# PDInjector.net
KiCad netlist of a schematic drawn in Altium Designer
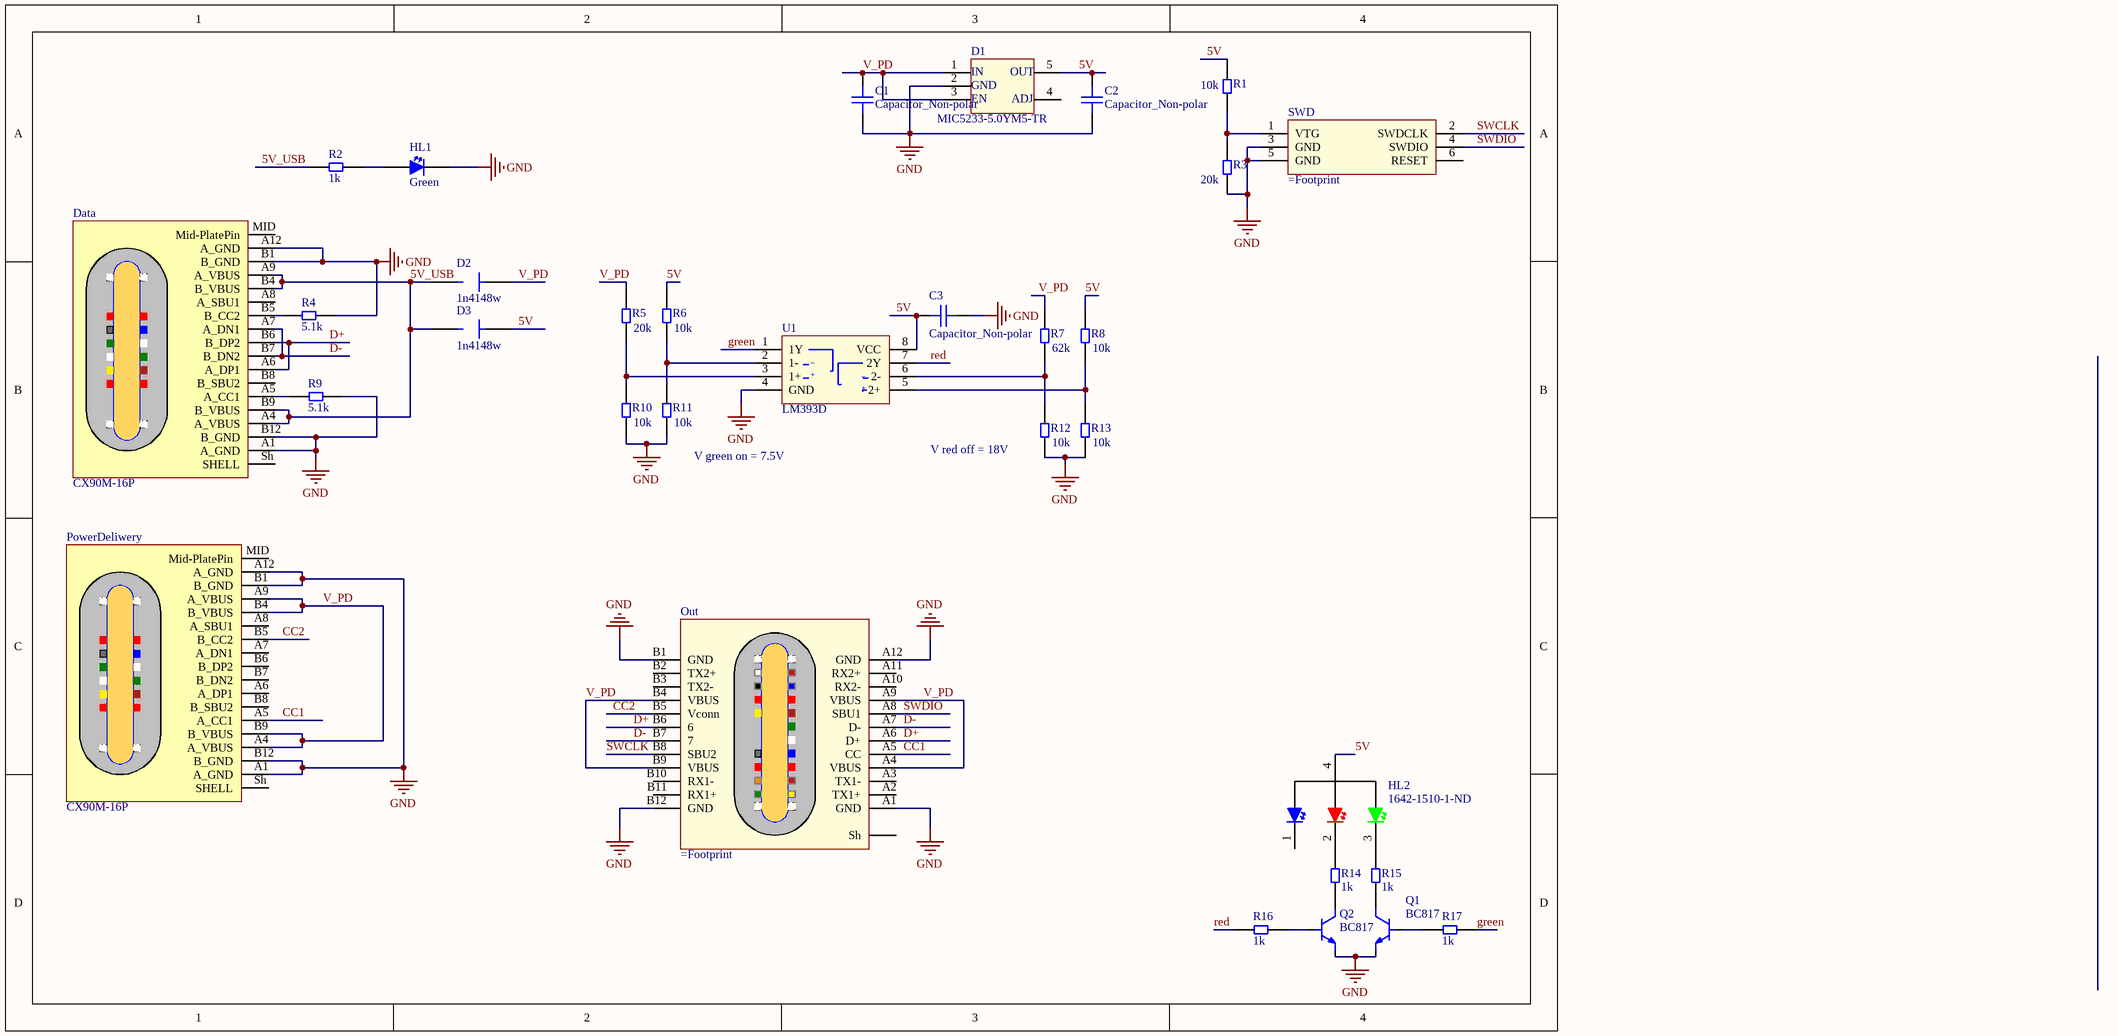
[diagram p0: PDInjector.SchDoc]

(export (version "E")
  (design (tool "Eeschema 10.0.6"))
  (components
    (comp (ref "C1")
      (value "Capacitor_Non-polar")
      (footprint "CAP_0402")
      (libsource (lib "PassiveComponents") (part "Capacitor_Non-polar"))
    )
    (comp (ref "C2")
      (value "Capacitor_Non-polar")
      (footprint "CAP_0402")
      (libsource (lib "PassiveComponents") (part "Capacitor_Non-polar"))
    )
    (comp (ref "C3")
      (value "Capacitor_Non-polar")
      (footprint "CAP_0402")
      (libsource (lib "PassiveComponents") (part "Capacitor_Non-polar"))
    )
    (comp (ref "D1")
      (value "MIC5233-5.0YM5-TR")
      (footprint "SOT23-5")
      (libsource (lib "PowerSupply lib ") (part "MIC5233-3.3YM5-TR LDO"))
    )
    (comp (ref "D2")
      (value "1n4148w")
      (footprint "SOD-123FL")
      (description "Different types of diodes")
      (libsource (lib "Semiconductors-Discretes") (part "DIOD"))
    )
    (comp (ref "D3")
      (value "1n4148w")
      (footprint "SOD-123FL")
      (description "Different types of diodes")
      (libsource (lib "Semiconductors-Discretes") (part "DIOD"))
    )
    (comp (ref "Data")
      (value "CX90M-16P")
      (footprint "USB_C_Hirose_CX90M-16P")
      (libsource (lib "Connectors") (part "USB_C_Hirose_CX90M-16P"))
    )
    (comp (ref "HL1")
      (value "Green")
      (footprint "LED_0603")
      (libsource (lib "OptoelectronicsDisplays") (part "SMD_LED"))
    )
    (comp (ref "HL2")
      (value "1642-1510-1-ND")
      (footprint "CL-505S-X-SD-T")
      (libsource (lib "OptoelectronicsDisplays") (part "1642-1510-1-ND"))
    )
    (comp (ref "Out")
      (value "~")
      (footprint "USB_TYPE-C_PLUG")
      (libsource (lib "Connectors") (part "USB Type-C Plug"))
    )
    (comp (ref "PowerDeliwery")
      (value "CX90M-16P")
      (footprint "USB_C_Hirose_CX90M-16P")
      (libsource (lib "Connectors") (part "USB_C_Hirose_CX90M-16P"))
    )
    (comp (ref "Q1")
      (value "BC817")
      (footprint "SOT23")
      (description "Transistor_NPN_SOT-23")
      (libsource (lib "Semiconductors-Discretes") (part "Transistor_NPN_SOT-23"))
    )
    (comp (ref "Q2")
      (value "BC817")
      (footprint "SOT23")
      (description "Transistor_NPN_SOT-23")
      (libsource (lib "Semiconductors-Discretes") (part "Transistor_NPN_SOT-23"))
    )
    (comp (ref "R1")
      (value "10k")
      (footprint "RES_0402")
      (libsource (lib "PassiveComponents") (part "Resistor"))
    )
    (comp (ref "R2")
      (value "1k")
      (footprint "RES_0402")
      (libsource (lib "PassiveComponents") (part "Resistor"))
    )
    (comp (ref "R3")
      (value "20k")
      (footprint "RES_0402")
      (libsource (lib "PassiveComponents") (part "Resistor"))
    )
    (comp (ref "R4")
      (value "5.1k")
      (footprint "RES_0402")
      (libsource (lib "PassiveComponents") (part "Resistor"))
    )
    (comp (ref "R5")
      (value "20k")
      (footprint "RES_0402")
      (libsource (lib "PassiveComponents") (part "Resistor"))
    )
    (comp (ref "R6")
      (value "10k")
      (footprint "RES_0402")
      (libsource (lib "PassiveComponents") (part "Resistor"))
    )
    (comp (ref "R7")
      (value "62k")
      (footprint "RES_0402")
      (libsource (lib "PassiveComponents") (part "Resistor"))
    )
    (comp (ref "R8")
      (value "10k")
      (footprint "RES_0402")
      (libsource (lib "PassiveComponents") (part "Resistor"))
    )
    (comp (ref "R9")
      (value "5.1k")
      (footprint "RES_0402")
      (libsource (lib "PassiveComponents") (part "Resistor"))
    )
    (comp (ref "R10")
      (value "10k")
      (footprint "RES_0402")
      (libsource (lib "PassiveComponents") (part "Resistor"))
    )
    (comp (ref "R11")
      (value "10k")
      (footprint "RES_0402")
      (libsource (lib "PassiveComponents") (part "Resistor"))
    )
    (comp (ref "R12")
      (value "10k")
      (footprint "RES_0402")
      (libsource (lib "PassiveComponents") (part "Resistor"))
    )
    (comp (ref "R13")
      (value "10k")
      (footprint "RES_0402")
      (libsource (lib "PassiveComponents") (part "Resistor"))
    )
    (comp (ref "R14")
      (value "1k")
      (footprint "RES_0402")
      (libsource (lib "PassiveComponents") (part "Resistor"))
    )
    (comp (ref "R15")
      (value "1k")
      (footprint "RES_0402")
      (libsource (lib "PassiveComponents") (part "Resistor"))
    )
    (comp (ref "R16")
      (value "1k")
      (footprint "RES_0402")
      (libsource (lib "PassiveComponents") (part "Resistor"))
    )
    (comp (ref "R17")
      (value "1k")
      (footprint "RES_0402")
      (libsource (lib "PassiveComponents") (part "Resistor"))
    )
    (comp (ref "SWD")
      (value "~")
      (footprint "MICRO-MATCH FOB.06P")
      (libsource (lib "Connectors") (part "MICRO-MATCH FOB.06P_nRF/STM32_SWD"))
    )
    (comp (ref "U1")
      (value "LM393D")
      (footprint "SOIC8(3.9)")
      (description "Dual OpAmp")
      (libsource (lib "AmplifiersAndComparators") (part "LM358"))
    )
  )
  (nets
    (net (code "1") (name "/5V") (class "Default")
      (node (ref "C2") (pin "2") (pinfunction "2_2") (pintype "passive"))
      (node (ref "C3") (pin "1") (pinfunction "1_1") (pintype "passive"))
      (node (ref "D1") (pin "5") (pintype "power_in"))
      (node (ref "D3") (pin "2") (pinfunction "Cathode_2") (pintype "passive"))
      (node (ref "HL2") (pin "4") (pinfunction "4_4") (pintype "passive"))
      (node (ref "R1") (pin "2") (pinfunction "2_2") (pintype "passive"))
      (node (ref "R6") (pin "2") (pinfunction "2_2") (pintype "passive"))
      (node (ref "R8") (pin "2") (pinfunction "2_2") (pintype "passive"))
      (node (ref "U1") (pin "8") (pinfunction "VCC_8") (pintype "passive"))
    )
    (net (code "2") (name "/5V_USB") (class "Default")
      (node (ref "D2") (pin "1") (pinfunction "Anode_1") (pintype "passive"))
      (node (ref "D3") (pin "1") (pinfunction "Anode_1") (pintype "passive"))
      (node (ref "Data") (pin "A4") (pinfunction "A_VBUS_A4") (pintype "passive"))
      (node (ref "Data") (pin "A9") (pinfunction "A_VBUS_A9") (pintype "passive"))
      (node (ref "Data") (pin "B4") (pinfunction "B_VBUS_B4") (pintype "passive"))
      (node (ref "Data") (pin "B9") (pinfunction "B_VBUS_B9") (pintype "passive"))
      (node (ref "R2") (pin "2") (pinfunction "2_2") (pintype "passive"))
    )
    (net (code "3") (name "/CC1") (class "Default")
      (node (ref "Out") (pin "A5") (pinfunction "CC_A5") (pintype "passive"))
      (node (ref "PowerDeliwery") (pin "A5") (pinfunction "A_CC1_A5") (pintype "passive"))
    )
    (net (code "4") (name "/CC2") (class "Default")
      (node (ref "Out") (pin "B5") (pinfunction "Vconn_B5") (pintype "passive"))
      (node (ref "PowerDeliwery") (pin "B5") (pinfunction "B_CC2_B5") (pintype "passive"))
    )
    (net (code "5") (name "/D+") (class "Default")
      (node (ref "Data") (pin "A6") (pinfunction "A_DP1_A6") (pintype "passive"))
      (node (ref "Data") (pin "B6") (pinfunction "B_DP2_B6") (pintype "passive"))
      (node (ref "Out") (pin "A6") (pinfunction "D+_A6") (pintype "passive"))
      (node (ref "Out") (pin "B6") (pinfunction "6_B6") (pintype "passive"))
    )
    (net (code "6") (name "/D-") (class "Default")
      (node (ref "Data") (pin "A7") (pinfunction "A_DN1_A7") (pintype "passive"))
      (node (ref "Data") (pin "B7") (pinfunction "B_DN2_B7") (pintype "passive"))
      (node (ref "Out") (pin "A7") (pinfunction "D-_A7") (pintype "passive"))
      (node (ref "Out") (pin "B7") (pinfunction "7_B7") (pintype "passive"))
    )
    (net (code "7") (name "/SWCLK") (class "Default")
      (node (ref "Out") (pin "B8") (pinfunction "SBU2_B8") (pintype "passive"))
      (node (ref "SWD") (pin "2") (pinfunction "SWDCLK_2") (pintype "passive"))
    )
    (net (code "8") (name "/SWDIO") (class "Default")
      (node (ref "Out") (pin "A8") (pinfunction "SBU1_A8") (pintype "passive"))
      (node (ref "SWD") (pin "4") (pinfunction "SWDIO_4") (pintype "passive"))
    )
    (net (code "9") (name "/V_PD") (class "Default")
      (node (ref "C1") (pin "2") (pinfunction "2_2") (pintype "passive"))
      (node (ref "D1") (pin "1") (pintype "power_in"))
      (node (ref "D1") (pin "3") (pintype "power_in"))
      (node (ref "D2") (pin "2") (pinfunction "Cathode_2") (pintype "passive"))
      (node (ref "Out") (pin "A4") (pinfunction "VBUS_A4") (pintype "passive"))
      (node (ref "Out") (pin "A9") (pinfunction "VBUS_A9") (pintype "passive"))
      (node (ref "Out") (pin "B4") (pinfunction "VBUS_B4") (pintype "passive"))
      (node (ref "Out") (pin "B9") (pinfunction "VBUS_B9") (pintype "passive"))
      (node (ref "PowerDeliwery") (pin "A4") (pinfunction "A_VBUS_A4") (pintype "passive"))
      (node (ref "PowerDeliwery") (pin "A9") (pinfunction "A_VBUS_A9") (pintype "passive"))
      (node (ref "PowerDeliwery") (pin "B4") (pinfunction "B_VBUS_B4") (pintype "passive"))
      (node (ref "PowerDeliwery") (pin "B9") (pinfunction "B_VBUS_B9") (pintype "passive"))
      (node (ref "R5") (pin "2") (pinfunction "2_2") (pintype "passive"))
      (node (ref "R7") (pin "2") (pinfunction "2_2") (pintype "passive"))
    )
    (net (code "10") (name "/green") (class "Default")
      (node (ref "R17") (pin "2") (pinfunction "2_2") (pintype "passive"))
      (node (ref "U1") (pin "1") (pinfunction "1Y_1") (pintype "passive"))
    )
    (net (code "11") (name "/red") (class "Default")
      (node (ref "R16") (pin "1") (pinfunction "1_1") (pintype "passive"))
      (node (ref "U1") (pin "7") (pinfunction "2Y_7") (pintype "passive"))
    )
    (net (code "12") (name "GND") (class "Default")
      (node (ref "C1") (pin "1") (pinfunction "1_1") (pintype "passive"))
      (node (ref "C2") (pin "1") (pinfunction "1_1") (pintype "passive"))
      (node (ref "C3") (pin "2") (pinfunction "2_2") (pintype "passive"))
      (node (ref "D1") (pin "2") (pintype "power_in"))
      (node (ref "Data") (pin "A1") (pinfunction "A_GND_A1") (pintype "passive"))
      (node (ref "Data") (pin "A12") (pinfunction "A_GND_A12") (pintype "passive"))
      (node (ref "Data") (pin "B1") (pinfunction "B_GND_B1") (pintype "passive"))
      (node (ref "Data") (pin "B12") (pinfunction "B_GND_B12") (pintype "passive"))
      (node (ref "HL1") (pin "2") (pinfunction "2_2") (pintype "passive"))
      (node (ref "Out") (pin "A1") (pinfunction "GND_A1") (pintype "passive"))
      (node (ref "Out") (pin "A12") (pinfunction "GND_A12") (pintype "passive"))
      (node (ref "Out") (pin "B1") (pinfunction "GND_B1") (pintype "passive"))
      (node (ref "Out") (pin "B12") (pinfunction "GND_B12") (pintype "passive"))
      (node (ref "PowerDeliwery") (pin "A1") (pinfunction "A_GND_A1") (pintype "passive"))
      (node (ref "PowerDeliwery") (pin "A12") (pinfunction "A_GND_A12") (pintype "passive"))
      (node (ref "PowerDeliwery") (pin "B1") (pinfunction "B_GND_B1") (pintype "passive"))
      (node (ref "PowerDeliwery") (pin "B12") (pinfunction "B_GND_B12") (pintype "passive"))
      (node (ref "Q1") (pin "2") (pinfunction "E_2") (pintype "passive"))
      (node (ref "Q2") (pin "2") (pinfunction "E_2") (pintype "passive"))
      (node (ref "R10") (pin "1") (pinfunction "1_1") (pintype "passive"))
      (node (ref "R11") (pin "1") (pinfunction "1_1") (pintype "passive"))
      (node (ref "R12") (pin "1") (pinfunction "1_1") (pintype "passive"))
      (node (ref "R13") (pin "1") (pinfunction "1_1") (pintype "passive"))
      (node (ref "R3") (pin "1") (pinfunction "1_1") (pintype "passive"))
      (node (ref "R4") (pin "1") (pinfunction "1_1") (pintype "passive"))
      (node (ref "R9") (pin "1") (pinfunction "1_1") (pintype "passive"))
      (node (ref "SWD") (pin "3") (pinfunction "GND_3") (pintype "passive"))
      (node (ref "SWD") (pin "5") (pinfunction "GND_5") (pintype "passive"))
      (node (ref "U1") (pin "4") (pinfunction "GND_4") (pintype "passive"))
    )
    (net (code "13") (name "Net-(Data-A_CC1)") (class "Default")
      (node (ref "Data") (pin "A5") (pinfunction "A_CC1_A5") (pintype "passive"))
      (node (ref "R9") (pin "2") (pinfunction "2_2") (pintype "passive"))
    )
    (net (code "14") (name "Net-(Data-B_CC2)") (class "Default")
      (node (ref "Data") (pin "B5") (pinfunction "B_CC2_B5") (pintype "passive"))
      (node (ref "R4") (pin "2") (pinfunction "2_2") (pintype "passive"))
    )
    (net (code "15") (name "Net-(HL1-Pad1)") (class "Default")
      (node (ref "HL1") (pin "1") (pinfunction "1_1") (pintype "passive"))
      (node (ref "R2") (pin "1") (pinfunction "1_1") (pintype "passive"))
    )
    (net (code "16") (name "Net-(HL2-Pad2)") (class "Default")
      (node (ref "HL2") (pin "2") (pinfunction "2_2") (pintype "passive"))
      (node (ref "R14") (pin "1") (pinfunction "1_1") (pintype "passive"))
    )
    (net (code "17") (name "Net-(HL2-Pad3)") (class "Default")
      (node (ref "HL2") (pin "3") (pinfunction "3_3") (pintype "passive"))
      (node (ref "R15") (pin "1") (pinfunction "1_1") (pintype "passive"))
    )
    (net (code "18") (name "Net-(Q1-B)") (class "Default")
      (node (ref "Q1") (pin "1") (pinfunction "B_1") (pintype "passive"))
      (node (ref "R17") (pin "1") (pinfunction "1_1") (pintype "passive"))
    )
    (net (code "19") (name "Net-(Q1-C)") (class "Default")
      (node (ref "Q1") (pin "3") (pinfunction "C_3") (pintype "passive"))
      (node (ref "R15") (pin "2") (pinfunction "2_2") (pintype "passive"))
    )
    (net (code "20") (name "Net-(Q2-B)") (class "Default")
      (node (ref "Q2") (pin "1") (pinfunction "B_1") (pintype "passive"))
      (node (ref "R16") (pin "2") (pinfunction "2_2") (pintype "passive"))
    )
    (net (code "21") (name "Net-(Q2-C)") (class "Default")
      (node (ref "Q2") (pin "3") (pinfunction "C_3") (pintype "passive"))
      (node (ref "R14") (pin "2") (pinfunction "2_2") (pintype "passive"))
    )
    (net (code "22") (name "Net-(SWD-VTG)") (class "Default")
      (node (ref "R1") (pin "1") (pinfunction "1_1") (pintype "passive"))
      (node (ref "R3") (pin "2") (pinfunction "2_2") (pintype "passive"))
      (node (ref "SWD") (pin "1") (pinfunction "VTG_1") (pintype "passive"))
    )
    (net (code "23") (name "Net-(U1-1+)") (class "Default")
      (node (ref "R10") (pin "2") (pinfunction "2_2") (pintype "passive"))
      (node (ref "R5") (pin "1") (pinfunction "1_1") (pintype "passive"))
      (node (ref "U1") (pin "3") (pinfunction "1+_3") (pintype "passive"))
    )
    (net (code "24") (name "Net-(U1-1-)") (class "Default")
      (node (ref "R11") (pin "2") (pinfunction "2_2") (pintype "passive"))
      (node (ref "R6") (pin "1") (pinfunction "1_1") (pintype "passive"))
      (node (ref "U1") (pin "2") (pinfunction "1-_2") (pintype "passive"))
    )
    (net (code "25") (name "Net-(U1-2+)") (class "Default")
      (node (ref "R13") (pin "2") (pinfunction "2_2") (pintype "passive"))
      (node (ref "R8") (pin "1") (pinfunction "1_1") (pintype "passive"))
      (node (ref "U1") (pin "5") (pinfunction "2+_5") (pintype "passive"))
    )
    (net (code "26") (name "Net-(U1-2-)") (class "Default")
      (node (ref "R12") (pin "2") (pinfunction "2_2") (pintype "passive"))
      (node (ref "R7") (pin "1") (pinfunction "1_1") (pintype "passive"))
      (node (ref "U1") (pin "6") (pinfunction "2-_6") (pintype "passive"))
    )
    (net (code "27") (name "unconnected-(D1-Pad4)") (class "Default")
      (node (ref "D1") (pin "4") (pintype "power_in"))
    )
    (net (code "28") (name "unconnected-(Data-A_SBU1-PadA8)") (class "Default")
      (node (ref "Data") (pin "A8") (pinfunction "A_SBU1_A8") (pintype "passive"))
    )
    (net (code "29") (name "unconnected-(Data-B_SBU2-PadB8)") (class "Default")
      (node (ref "Data") (pin "B8") (pinfunction "B_SBU2_B8") (pintype "passive"))
    )
    (net (code "30") (name "unconnected-(Data-Mid-PlatePin-PadMID)") (class "Default")
      (node (ref "Data") (pin "MID") (pinfunction "Mid-PlatePin_MID") (pintype "passive"))
    )
    (net (code "31") (name "unconnected-(Data-SHELL-PadSh)") (class "Default")
      (node (ref "Data") (pin "Sh") (pinfunction "SHELL_Sh") (pintype "passive"))
    )
    (net (code "32") (name "unconnected-(HL2-Pad1)") (class "Default")
      (node (ref "HL2") (pin "1") (pinfunction "1_1") (pintype "passive"))
    )
    (net (code "33") (name "unconnected-(Out-PadSh)") (class "Default")
      (node (ref "Out") (pin "Sh") (pinfunction "Sh_Sh") (pintype "passive"))
    )
    (net (code "34") (name "unconnected-(Out-RX1+-PadB11)") (class "Default")
      (node (ref "Out") (pin "B11") (pinfunction "RX1+_B11") (pintype "passive"))
    )
    (net (code "35") (name "unconnected-(Out-RX1--PadB10)") (class "Default")
      (node (ref "Out") (pin "B10") (pinfunction "RX1-_B10") (pintype "passive"))
    )
    (net (code "36") (name "unconnected-(Out-RX2+-PadA11)") (class "Default")
      (node (ref "Out") (pin "A11") (pinfunction "RX2+_A11") (pintype "passive"))
    )
    (net (code "37") (name "unconnected-(Out-RX2--PadA10)") (class "Default")
      (node (ref "Out") (pin "A10") (pinfunction "RX2-_A10") (pintype "passive"))
    )
    (net (code "38") (name "unconnected-(Out-TX1+-PadA2)") (class "Default")
      (node (ref "Out") (pin "A2") (pinfunction "TX1+_A2") (pintype "passive"))
    )
    (net (code "39") (name "unconnected-(Out-TX1--PadA3)") (class "Default")
      (node (ref "Out") (pin "A3") (pinfunction "TX1-_A3") (pintype "passive"))
    )
    (net (code "40") (name "unconnected-(Out-TX2+-PadB2)") (class "Default")
      (node (ref "Out") (pin "B2") (pinfunction "TX2+_B2") (pintype "passive"))
    )
    (net (code "41") (name "unconnected-(Out-TX2--PadB3)") (class "Default")
      (node (ref "Out") (pin "B3") (pinfunction "TX2-_B3") (pintype "passive"))
    )
    (net (code "42") (name "unconnected-(PowerDeliwery-A_DN1-PadA7)") (class "Default")
      (node (ref "PowerDeliwery") (pin "A7") (pinfunction "A_DN1_A7") (pintype "passive"))
    )
    (net (code "43") (name "unconnected-(PowerDeliwery-A_DP1-PadA6)") (class "Default")
      (node (ref "PowerDeliwery") (pin "A6") (pinfunction "A_DP1_A6") (pintype "passive"))
    )
    (net (code "44") (name "unconnected-(PowerDeliwery-A_SBU1-PadA8)") (class "Default")
      (node (ref "PowerDeliwery") (pin "A8") (pinfunction "A_SBU1_A8") (pintype "passive"))
    )
    (net (code "45") (name "unconnected-(PowerDeliwery-B_DN2-PadB7)") (class "Default")
      (node (ref "PowerDeliwery") (pin "B7") (pinfunction "B_DN2_B7") (pintype "passive"))
    )
    (net (code "46") (name "unconnected-(PowerDeliwery-B_DP2-PadB6)") (class "Default")
      (node (ref "PowerDeliwery") (pin "B6") (pinfunction "B_DP2_B6") (pintype "passive"))
    )
    (net (code "47") (name "unconnected-(PowerDeliwery-B_SBU2-PadB8)") (class "Default")
      (node (ref "PowerDeliwery") (pin "B8") (pinfunction "B_SBU2_B8") (pintype "passive"))
    )
    (net (code "48") (name "unconnected-(PowerDeliwery-Mid-PlatePin-PadMID)") (class "Default")
      (node (ref "PowerDeliwery") (pin "MID") (pinfunction "Mid-PlatePin_MID") (pintype "passive"))
    )
    (net (code "49") (name "unconnected-(PowerDeliwery-SHELL-PadSh)") (class "Default")
      (node (ref "PowerDeliwery") (pin "Sh") (pinfunction "SHELL_Sh") (pintype "passive"))
    )
    (net (code "50") (name "unconnected-(SWD-RESET-Pad6)") (class "Default")
      (node (ref "SWD") (pin "6") (pinfunction "RESET_6") (pintype "passive"))
    )
  )
)
